# ESP32_Extension_Board_v1_0.net
KiCad netlist of a schematic drawn in EAGLE
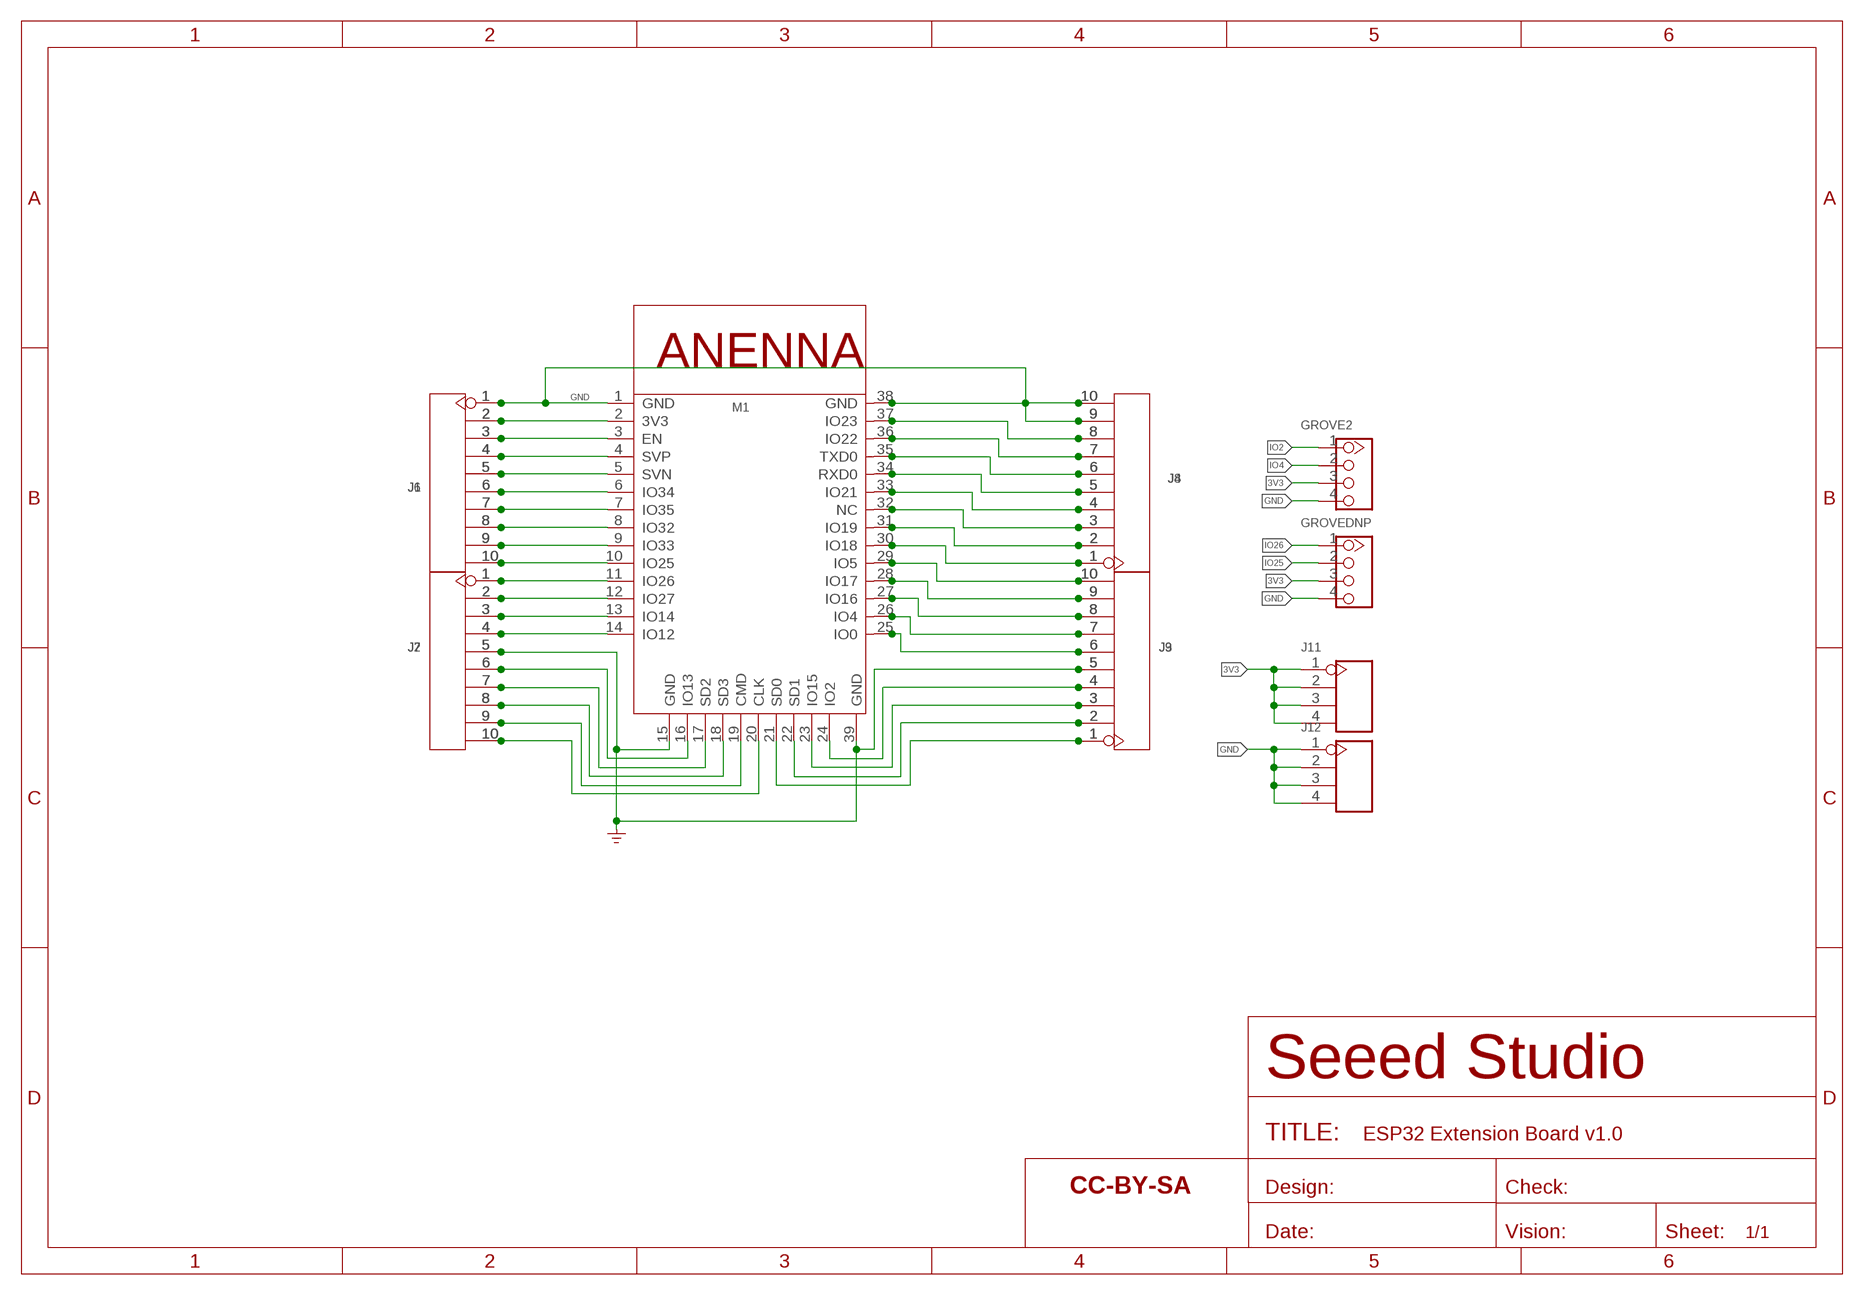
[diagram p0: schematic, sheet 1]

(export (version "E")
  (design (tool "Eeschema 10.0.6"))
  (components
    (comp (ref "FR2")
      (value "SEEEDSTUDIO-OPEN-SCH-FRAME")
      (footprint "eagle-import:SEEEDSTUDIO-PCB-FRAME")
      (libsource (lib "eagle-import") (part "SEEEDSTUDIO-OPEN-SCH-FRAME"))
    )
    (comp (ref "GROVE")
      (value "DNP")
      (footprint "eagle-import:HW4-2.0")
      (libsource (lib "eagle-import") (part "GROVE-CONNECTOR-DIP-2.0"))
    )
    (comp (ref "GROVE2")
      (value "GROVE-CONNECTOR-DIP-2.0")
      (footprint "eagle-import:HW4-2.0")
      (libsource (lib "eagle-import") (part "GROVE-CONNECTOR-DIP-2.0"))
    )
    (comp (ref "J1")
      (value "HEADER-10P-2.54")
      (footprint "eagle-import:H10-2.54")
      (libsource (lib "eagle-import") (part "HEADER-10P-2.54"))
    )
    (comp (ref "J2")
      (value "HEADER-10P-2.54")
      (footprint "eagle-import:H10-2.54")
      (libsource (lib "eagle-import") (part "HEADER-10P-2.54"))
    )
    (comp (ref "J3")
      (value "HEADER-10P-2.54")
      (footprint "eagle-import:H10-2.54")
      (libsource (lib "eagle-import") (part "HEADER-10P-2.54"))
    )
    (comp (ref "J4")
      (value "HEADER-10P-2.54")
      (footprint "eagle-import:H10-2.54")
      (libsource (lib "eagle-import") (part "HEADER-10P-2.54"))
    )
    (comp (ref "J6")
      (value "HEADER-10P-2.54")
      (footprint "eagle-import:H10-2.54")
      (libsource (lib "eagle-import") (part "HEADER-10P-2.54"))
    )
    (comp (ref "J7")
      (value "HEADER-10P-2.54")
      (footprint "eagle-import:H10-2.54")
      (libsource (lib "eagle-import") (part "HEADER-10P-2.54"))
    )
    (comp (ref "J8")
      (value "HEADER-10P-2.54")
      (footprint "eagle-import:H10-2.54")
      (libsource (lib "eagle-import") (part "HEADER-10P-2.54"))
    )
    (comp (ref "J9")
      (value "HEADER-10P-2.54")
      (footprint "eagle-import:H10-2.54")
      (libsource (lib "eagle-import") (part "HEADER-10P-2.54"))
    )
    (comp (ref "J11")
      (value "HEADER-4P-65/35MIL")
      (footprint "eagle-import:H4-2.54")
      (libsource (lib "eagle-import") (part "HEADER-4P-65/35MIL"))
    )
    (comp (ref "J12")
      (value "HEADER-4P-65/35MIL")
      (footprint "eagle-import:H4-2.54")
      (libsource (lib "eagle-import") (part "HEADER-4P-65/35MIL"))
    )
    (comp (ref "M1")
      (value "MODULE-WIFI-ESP-3212-38+1")
      (footprint "eagle-import:MODULE38P-1.3-18X25.5MM")
      (libsource (lib "eagle-import") (part "MODULE-WIFI-ESP-3212-38+1"))
    )
  )
  (nets
    (net (code "1") (name "3V3") (class "Default")
      (node (ref "GROVE") (pin "3") (pinfunction "3_3") (pintype "bidirectional"))
      (node (ref "GROVE2") (pin "3") (pinfunction "3_3") (pintype "bidirectional"))
      (node (ref "J1") (pin "2") (pinfunction "2_2") (pintype "bidirectional"))
      (node (ref "J11") (pin "1") (pinfunction "P$1_1") (pintype "bidirectional"))
      (node (ref "J11") (pin "2") (pinfunction "P$2_2") (pintype "bidirectional"))
      (node (ref "J11") (pin "3") (pinfunction "P$3_3") (pintype "bidirectional"))
      (node (ref "J11") (pin "4") (pinfunction "P$4_4") (pintype "bidirectional"))
      (node (ref "J6") (pin "2") (pinfunction "2_2") (pintype "bidirectional"))
      (node (ref "M1") (pin "2") (pinfunction "3V3_2") (pintype "bidirectional"))
    )
    (net (code "2") (name "GND") (class "Default")
      (node (ref "GROVE") (pin "4") (pinfunction "4_4") (pintype "bidirectional"))
      (node (ref "GROVE2") (pin "4") (pinfunction "4_4") (pintype "bidirectional"))
      (node (ref "J1") (pin "1") (pinfunction "1_1") (pintype "bidirectional"))
      (node (ref "J12") (pin "1") (pinfunction "P$1_1") (pintype "bidirectional"))
      (node (ref "J12") (pin "2") (pinfunction "P$2_2") (pintype "bidirectional"))
      (node (ref "J12") (pin "3") (pinfunction "P$3_3") (pintype "bidirectional"))
      (node (ref "J12") (pin "4") (pinfunction "P$4_4") (pintype "bidirectional"))
      (node (ref "J2") (pin "5") (pinfunction "5_5") (pintype "bidirectional"))
      (node (ref "J3") (pin "5") (pinfunction "5_5") (pintype "bidirectional"))
      (node (ref "J4") (pin "10") (pinfunction "10_10") (pintype "bidirectional"))
      (node (ref "J4") (pin "9") (pinfunction "9_9") (pintype "bidirectional"))
      (node (ref "J6") (pin "1") (pinfunction "1_1") (pintype "bidirectional"))
      (node (ref "J7") (pin "5") (pinfunction "5_5") (pintype "bidirectional"))
      (node (ref "J8") (pin "10") (pinfunction "10_10") (pintype "bidirectional"))
      (node (ref "J8") (pin "9") (pinfunction "9_9") (pintype "bidirectional"))
      (node (ref "J9") (pin "5") (pinfunction "5_5") (pintype "bidirectional"))
      (node (ref "M1") (pin "1") (pinfunction "GND_1") (pintype "bidirectional"))
      (node (ref "M1") (pin "15") (pinfunction "GND_15") (pintype "bidirectional"))
      (node (ref "M1") (pin "38") (pinfunction "GND_38") (pintype "bidirectional"))
      (node (ref "M1") (pin "39") (pinfunction "GND_39") (pintype "bidirectional"))
    )
    (net (code "3") (name "IO2") (class "Default")
      (node (ref "GROVE2") (pin "1") (pinfunction "1_1") (pintype "bidirectional"))
      (node (ref "J3") (pin "4") (pinfunction "4_4") (pintype "bidirectional"))
      (node (ref "J9") (pin "4") (pinfunction "4_4") (pintype "bidirectional"))
      (node (ref "M1") (pin "24") (pinfunction "IO2_24") (pintype "bidirectional"))
    )
    (net (code "4") (name "IO4") (class "Default")
      (node (ref "GROVE2") (pin "2") (pinfunction "2_2") (pintype "bidirectional"))
      (node (ref "J3") (pin "7") (pinfunction "7_7") (pintype "bidirectional"))
      (node (ref "J9") (pin "7") (pinfunction "7_7") (pintype "bidirectional"))
      (node (ref "M1") (pin "26") (pinfunction "IO4_26") (pintype "bidirectional"))
    )
    (net (code "5") (name "IO25") (class "Default")
      (node (ref "GROVE") (pin "2") (pinfunction "2_2") (pintype "bidirectional"))
      (node (ref "J1") (pin "10") (pinfunction "10_10") (pintype "bidirectional"))
      (node (ref "J6") (pin "10") (pinfunction "10_10") (pintype "bidirectional"))
      (node (ref "M1") (pin "10") (pinfunction "IO25_10") (pintype "bidirectional"))
    )
    (net (code "6") (name "IO26") (class "Default")
      (node (ref "GROVE") (pin "1") (pinfunction "1_1") (pintype "bidirectional"))
      (node (ref "J2") (pin "1") (pinfunction "1_1") (pintype "bidirectional"))
      (node (ref "J7") (pin "1") (pinfunction "1_1") (pintype "bidirectional"))
      (node (ref "M1") (pin "11") (pinfunction "IO26_11") (pintype "bidirectional"))
    )
    (net (code "7") (name "Net-(M1-CLK)") (class "Default")
      (node (ref "J2") (pin "10") (pinfunction "10_10") (pintype "bidirectional"))
      (node (ref "J7") (pin "10") (pinfunction "10_10") (pintype "bidirectional"))
      (node (ref "M1") (pin "20") (pinfunction "CLK_20") (pintype "bidirectional"))
    )
    (net (code "8") (name "Net-(M1-CMD)") (class "Default")
      (node (ref "J2") (pin "9") (pinfunction "9_9") (pintype "bidirectional"))
      (node (ref "J7") (pin "9") (pinfunction "9_9") (pintype "bidirectional"))
      (node (ref "M1") (pin "19") (pinfunction "CMD_19") (pintype "bidirectional"))
    )
    (net (code "9") (name "Net-(M1-EN)") (class "Default")
      (node (ref "J1") (pin "3") (pinfunction "3_3") (pintype "bidirectional"))
      (node (ref "J6") (pin "3") (pinfunction "3_3") (pintype "bidirectional"))
      (node (ref "M1") (pin "3") (pinfunction "EN_3") (pintype "bidirectional"))
    )
    (net (code "10") (name "Net-(M1-IO0)") (class "Default")
      (node (ref "J3") (pin "6") (pinfunction "6_6") (pintype "bidirectional"))
      (node (ref "J9") (pin "6") (pinfunction "6_6") (pintype "bidirectional"))
      (node (ref "M1") (pin "25") (pinfunction "IO0_25") (pintype "bidirectional"))
    )
    (net (code "11") (name "Net-(M1-IO5)") (class "Default")
      (node (ref "J3") (pin "10") (pinfunction "10_10") (pintype "bidirectional"))
      (node (ref "J9") (pin "10") (pinfunction "10_10") (pintype "bidirectional"))
      (node (ref "M1") (pin "29") (pinfunction "IO5_29") (pintype "bidirectional"))
    )
    (net (code "12") (name "Net-(M1-IO12)") (class "Default")
      (node (ref "J2") (pin "4") (pinfunction "4_4") (pintype "bidirectional"))
      (node (ref "J7") (pin "4") (pinfunction "4_4") (pintype "bidirectional"))
      (node (ref "M1") (pin "14") (pinfunction "IO12_14") (pintype "bidirectional"))
    )
    (net (code "13") (name "Net-(M1-IO13)") (class "Default")
      (node (ref "J2") (pin "6") (pinfunction "6_6") (pintype "bidirectional"))
      (node (ref "J7") (pin "6") (pinfunction "6_6") (pintype "bidirectional"))
      (node (ref "M1") (pin "16") (pinfunction "IO13_16") (pintype "bidirectional"))
    )
    (net (code "14") (name "Net-(M1-IO14)") (class "Default")
      (node (ref "J2") (pin "3") (pinfunction "3_3") (pintype "bidirectional"))
      (node (ref "J7") (pin "3") (pinfunction "3_3") (pintype "bidirectional"))
      (node (ref "M1") (pin "13") (pinfunction "IO14_13") (pintype "bidirectional"))
    )
    (net (code "15") (name "Net-(M1-IO15)") (class "Default")
      (node (ref "J3") (pin "3") (pinfunction "3_3") (pintype "bidirectional"))
      (node (ref "J9") (pin "3") (pinfunction "3_3") (pintype "bidirectional"))
      (node (ref "M1") (pin "23") (pinfunction "IO15_23") (pintype "bidirectional"))
    )
    (net (code "16") (name "Net-(M1-IO16)") (class "Default")
      (node (ref "J3") (pin "8") (pinfunction "8_8") (pintype "bidirectional"))
      (node (ref "J9") (pin "8") (pinfunction "8_8") (pintype "bidirectional"))
      (node (ref "M1") (pin "27") (pinfunction "IO16_27") (pintype "bidirectional"))
    )
    (net (code "17") (name "Net-(M1-IO17)") (class "Default")
      (node (ref "J3") (pin "9") (pinfunction "9_9") (pintype "bidirectional"))
      (node (ref "J9") (pin "9") (pinfunction "9_9") (pintype "bidirectional"))
      (node (ref "M1") (pin "28") (pinfunction "IO17_28") (pintype "bidirectional"))
    )
    (net (code "18") (name "Net-(M1-IO18)") (class "Default")
      (node (ref "J4") (pin "1") (pinfunction "1_1") (pintype "bidirectional"))
      (node (ref "J8") (pin "1") (pinfunction "1_1") (pintype "bidirectional"))
      (node (ref "M1") (pin "30") (pinfunction "IO18_30") (pintype "bidirectional"))
    )
    (net (code "19") (name "Net-(M1-IO19)") (class "Default")
      (node (ref "J4") (pin "2") (pinfunction "2_2") (pintype "bidirectional"))
      (node (ref "J8") (pin "2") (pinfunction "2_2") (pintype "bidirectional"))
      (node (ref "M1") (pin "31") (pinfunction "IO19_31") (pintype "bidirectional"))
    )
    (net (code "20") (name "Net-(M1-IO21)") (class "Default")
      (node (ref "J4") (pin "4") (pinfunction "4_4") (pintype "bidirectional"))
      (node (ref "J8") (pin "4") (pinfunction "4_4") (pintype "bidirectional"))
      (node (ref "M1") (pin "33") (pinfunction "IO21_33") (pintype "bidirectional"))
    )
    (net (code "21") (name "Net-(M1-IO22)") (class "Default")
      (node (ref "J4") (pin "7") (pinfunction "7_7") (pintype "bidirectional"))
      (node (ref "J8") (pin "7") (pinfunction "7_7") (pintype "bidirectional"))
      (node (ref "M1") (pin "36") (pinfunction "IO22_36") (pintype "bidirectional"))
    )
    (net (code "22") (name "Net-(M1-IO23)") (class "Default")
      (node (ref "J4") (pin "8") (pinfunction "8_8") (pintype "bidirectional"))
      (node (ref "J8") (pin "8") (pinfunction "8_8") (pintype "bidirectional"))
      (node (ref "M1") (pin "37") (pinfunction "IO23_37") (pintype "bidirectional"))
    )
    (net (code "23") (name "Net-(M1-IO27)") (class "Default")
      (node (ref "J2") (pin "2") (pinfunction "2_2") (pintype "bidirectional"))
      (node (ref "J7") (pin "2") (pinfunction "2_2") (pintype "bidirectional"))
      (node (ref "M1") (pin "12") (pinfunction "IO27_12") (pintype "bidirectional"))
    )
    (net (code "24") (name "Net-(M1-IO32)") (class "Default")
      (node (ref "J1") (pin "8") (pinfunction "8_8") (pintype "bidirectional"))
      (node (ref "J6") (pin "8") (pinfunction "8_8") (pintype "bidirectional"))
      (node (ref "M1") (pin "8") (pinfunction "IO32_8") (pintype "bidirectional"))
    )
    (net (code "25") (name "Net-(M1-IO33)") (class "Default")
      (node (ref "J1") (pin "9") (pinfunction "9_9") (pintype "bidirectional"))
      (node (ref "J6") (pin "9") (pinfunction "9_9") (pintype "bidirectional"))
      (node (ref "M1") (pin "9") (pinfunction "IO33_9") (pintype "bidirectional"))
    )
    (net (code "26") (name "Net-(M1-IO34)") (class "Default")
      (node (ref "J1") (pin "6") (pinfunction "6_6") (pintype "bidirectional"))
      (node (ref "J6") (pin "6") (pinfunction "6_6") (pintype "bidirectional"))
      (node (ref "M1") (pin "6") (pinfunction "IO34_6") (pintype "bidirectional"))
    )
    (net (code "27") (name "Net-(M1-IO35)") (class "Default")
      (node (ref "J1") (pin "7") (pinfunction "7_7") (pintype "bidirectional"))
      (node (ref "J6") (pin "7") (pinfunction "7_7") (pintype "bidirectional"))
      (node (ref "M1") (pin "7") (pinfunction "IO35_7") (pintype "bidirectional"))
    )
    (net (code "28") (name "Net-(M1-NC)") (class "Default")
      (node (ref "J4") (pin "3") (pinfunction "3_3") (pintype "bidirectional"))
      (node (ref "J8") (pin "3") (pinfunction "3_3") (pintype "bidirectional"))
      (node (ref "M1") (pin "32") (pinfunction "NC_32") (pintype "bidirectional"))
    )
    (net (code "29") (name "Net-(M1-RXD0)") (class "Default")
      (node (ref "J4") (pin "5") (pinfunction "5_5") (pintype "bidirectional"))
      (node (ref "J8") (pin "5") (pinfunction "5_5") (pintype "bidirectional"))
      (node (ref "M1") (pin "34") (pinfunction "RXD0_34") (pintype "bidirectional"))
    )
    (net (code "30") (name "Net-(M1-SD0)") (class "Default")
      (node (ref "J3") (pin "1") (pinfunction "1_1") (pintype "bidirectional"))
      (node (ref "J9") (pin "1") (pinfunction "1_1") (pintype "bidirectional"))
      (node (ref "M1") (pin "21") (pinfunction "SD0_21") (pintype "bidirectional"))
    )
    (net (code "31") (name "Net-(M1-SD1)") (class "Default")
      (node (ref "J3") (pin "2") (pinfunction "2_2") (pintype "bidirectional"))
      (node (ref "J9") (pin "2") (pinfunction "2_2") (pintype "bidirectional"))
      (node (ref "M1") (pin "22") (pinfunction "SD1_22") (pintype "bidirectional"))
    )
    (net (code "32") (name "Net-(M1-SD2)") (class "Default")
      (node (ref "J2") (pin "7") (pinfunction "7_7") (pintype "bidirectional"))
      (node (ref "J7") (pin "7") (pinfunction "7_7") (pintype "bidirectional"))
      (node (ref "M1") (pin "17") (pinfunction "SD2_17") (pintype "bidirectional"))
    )
    (net (code "33") (name "Net-(M1-SD3)") (class "Default")
      (node (ref "J2") (pin "8") (pinfunction "8_8") (pintype "bidirectional"))
      (node (ref "J7") (pin "8") (pinfunction "8_8") (pintype "bidirectional"))
      (node (ref "M1") (pin "18") (pinfunction "SD3_18") (pintype "bidirectional"))
    )
    (net (code "34") (name "Net-(M1-SVN)") (class "Default")
      (node (ref "J1") (pin "5") (pinfunction "5_5") (pintype "bidirectional"))
      (node (ref "J6") (pin "5") (pinfunction "5_5") (pintype "bidirectional"))
      (node (ref "M1") (pin "5") (pinfunction "SVN_5") (pintype "bidirectional"))
    )
    (net (code "35") (name "Net-(M1-SVP)") (class "Default")
      (node (ref "J1") (pin "4") (pinfunction "4_4") (pintype "bidirectional"))
      (node (ref "J6") (pin "4") (pinfunction "4_4") (pintype "bidirectional"))
      (node (ref "M1") (pin "4") (pinfunction "SVP_4") (pintype "bidirectional"))
    )
    (net (code "36") (name "Net-(M1-TXD0)") (class "Default")
      (node (ref "J4") (pin "6") (pinfunction "6_6") (pintype "bidirectional"))
      (node (ref "J8") (pin "6") (pinfunction "6_6") (pintype "bidirectional"))
      (node (ref "M1") (pin "35") (pinfunction "TXD0_35") (pintype "bidirectional"))
    )
  )
)
